# PoESP_ConnectorBoard.net
KiCad netlist of a schematic drawn in Altium Designer
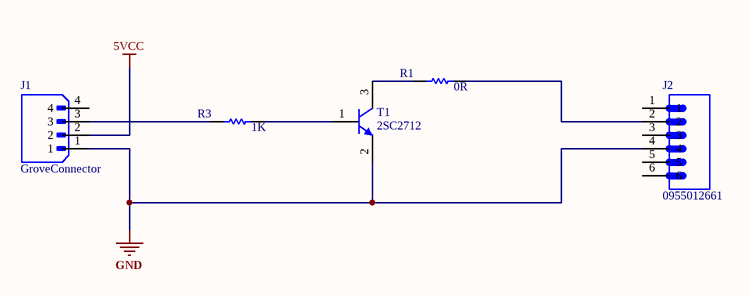
[diagram p0: PoESP_ConnectorBoard.SchDoc]

(export (version "E")
  (design (tool "Eeschema 10.0.6"))
  (components
    (comp (ref "J1")
      (value "GroveConnector")
      (footprint "SEEEDSTUDIO_114020164")
      (description "GROVE FEMALE HEADER R/A 20PACK")
      (fields (field (name "MF") "Seeed Technology Co., Ltd") (field (name "MP") "114020164"))
      (libsource (lib "PoESP_ConnectorBoard") (part "114020164"))
    )
    (comp (ref "J2")
      (value "0955012661")
      (footprint "MOLEX_0955012661")
      (description "Jack Modular Connector 6p6c (RJ11, RJ12, RJ14, RJ25) 90Â° Angle (Right) Unshielded Cat3")
      (fields (field (name "MF") "Molex"))
      (libsource (lib "PoESP_ConnectorBoard") (part "0955012661"))
    )
    (comp (ref "R1")
      (value "0R")
      (footprint "RES-0603")
      (libsource (lib "PoESP_ConnectorBoard") (part "RES"))
    )
    (comp (ref "R3")
      (value "1K")
      (footprint "RES-0603")
      (libsource (lib "PoESP_ConnectorBoard") (part "RES"))
    )
    (comp (ref "T1")
      (value "2SC2712")
      (footprint "SOT23-3D")
      (description "NPN Bipolar Transistor")
      (fields
        (field (name "MANUFACTURER_PART_NUMBER") "BSR14")
        (field (name "MANUFACTURER") "ON SEMICONDUCTOR")
      )
      (libsource (lib "PoESP_ConnectorBoard") (part "NPN-SOT23"))
    )
  )
  (nets
    (net (code "1") (name "5VCC") (class "Default")
      (node (ref "J1") (pin "2") (pinfunction "2_2") (pintype "passive"))
    )
    (net (code "2") (name "GND") (class "Default")
      (node (ref "J1") (pin "1") (pinfunction "1_1") (pintype "passive"))
      (node (ref "J2") (pin "4") (pinfunction "4_4") (pintype "passive"))
      (node (ref "T1") (pin "2") (pinfunction "E_2") (pintype "passive"))
    )
    (net (code "3") (name "Net-(J1-Pad3)") (class "Default")
      (node (ref "J1") (pin "3") (pinfunction "3_3") (pintype "passive"))
      (node (ref "R3") (pin "1") (pintype "passive"))
    )
    (net (code "4") (name "Net-(J2-Pad2)") (class "Default")
      (node (ref "J2") (pin "2") (pinfunction "2_2") (pintype "passive"))
      (node (ref "R1") (pin "2") (pintype "passive"))
    )
    (net (code "5") (name "Net-(T1-B)") (class "Default")
      (node (ref "R3") (pin "2") (pintype "passive"))
      (node (ref "T1") (pin "1") (pinfunction "B_1") (pintype "passive"))
    )
    (net (code "6") (name "Net-(T1-C)") (class "Default")
      (node (ref "R1") (pin "1") (pintype "passive"))
      (node (ref "T1") (pin "3") (pinfunction "C_3") (pintype "passive"))
    )
    (net (code "7") (name "unconnected-(J1-Pad4)") (class "Default")
      (node (ref "J1") (pin "4") (pinfunction "4_4") (pintype "passive"))
    )
    (net (code "8") (name "unconnected-(J2-Pad1)") (class "Default")
      (node (ref "J2") (pin "1") (pinfunction "1_1") (pintype "passive"))
    )
    (net (code "9") (name "unconnected-(J2-Pad3)") (class "Default")
      (node (ref "J2") (pin "3") (pinfunction "3_3") (pintype "passive"))
    )
    (net (code "10") (name "unconnected-(J2-Pad5)") (class "Default")
      (node (ref "J2") (pin "5") (pinfunction "5_5") (pintype "passive"))
    )
    (net (code "11") (name "unconnected-(J2-Pad6)") (class "Default")
      (node (ref "J2") (pin "6") (pinfunction "6_6") (pintype "passive"))
    )
  )
)
